# Sound_SCH.net
KiCad netlist of a schematic drawn in Altium Designer
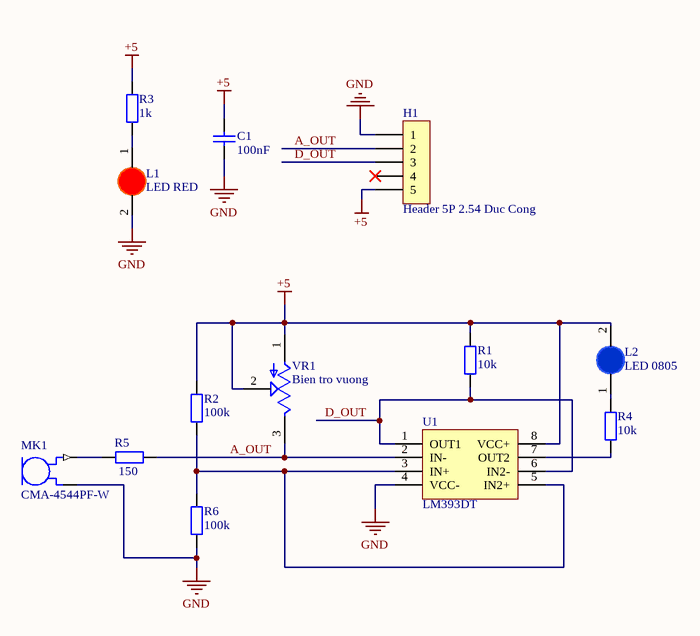
[diagram p0: Sound_SCH.SchDoc]

(export (version "E")
  (design (tool "Eeschema 10.0.6"))
  (components
    (comp (ref "C1")
      (value "100nF")
      (footprint "tu 0603")
      (description "Dán")
      (libsource (lib "namnt_Lib") (part "Tu 0603 104 50V 10%"))
    )
    (comp (ref "H1")
      (value "Header 5P 2.54 Duc Cong")
      (footprint "Header 5P DC 2.54")
      (description "Cắm")
      (libsource (lib "namnt_Lib") (part "Header 5P 2.54 Duc Cong"))
    )
    (comp (ref "L1")
      (value "LED RED")
      (footprint "LED-0805-Red")
      (description "Dán")
      (libsource (lib "namnt_Lib") (part "LED 0805 Do"))
    )
    (comp (ref "L2")
      (value "LED 0805")
      (footprint "LED-0805-Blue")
      (description "Dán")
      (libsource (lib "namnt_Lib") (part "LED 0805 Xanh Duong"))
    )
    (comp (ref "MK1")
      (value "CMA-4544PF-W")
      (footprint "MIC_CMA-4544PF-W")
      (description "9.7 mm, Omnidirectional, PCB Mount, 3.0 Vdc, Electret Condenser Microphone")
      (fields (field (name "MF") "Same Sky"))
      (libsource (lib "namnt_Lib") (part "CMA-4544PF-W"))
    )
    (comp (ref "R1")
      (value "10k")
      (footprint "tro smd 0603")
      (description "Dán")
      (libsource (lib "namnt_Lib") (part "Tro 0603 5% 100k"))
    )
    (comp (ref "R2")
      (value "100k")
      (footprint "tro smd 0603")
      (description "Dán")
      (libsource (lib "namnt_Lib") (part "Tro 0603 5% 100k"))
    )
    (comp (ref "R3")
      (value "1k")
      (footprint "tro smd 0603")
      (description "Dán")
      (libsource (lib "namnt_Lib") (part "Tro 0603 1% 1k"))
    )
    (comp (ref "R4")
      (value "10k")
      (footprint "tro smd 0603")
      (description "Dán")
      (libsource (lib "namnt_Lib") (part "Tro 0603 5% 100k"))
    )
    (comp (ref "R5")
      (value "150")
      (footprint "tro smd 0603")
      (description "Dán")
      (libsource (lib "namnt_Lib") (part "Tro 0603 5% 150R"))
    )
    (comp (ref "R6")
      (value "100k")
      (footprint "tro smd 0603")
      (description "Dán")
      (libsource (lib "namnt_Lib") (part "Tro 0603 5% 100k"))
    )
    (comp (ref "U1")
      (value "LM393DT")
      (footprint "SOIC8_50_328_25X90_SMT")
      (description "Comparator General Purpose CMOS, DTL, ECL, MOS, Open-Collector, TTL 8-SO")
      (fields (field (name "MANUFACTURER") "Texas Instruments"))
      (libsource (lib "namnt_Lib") (part "IC_LM393DT"))
    )
    (comp (ref "VR1")
      (value "Bien tro vuong")
      (footprint "TRIM_3362P-1-102")
      (description "TRIMMER - 1/4in SQ ST CERMET ¦ Bourns 3362P-1-102")
      (fields (field (name "MF") "Bourns") (field (name "MP") "3362P-1-102"))
      (libsource (lib "namnt_Lib") (part "Bien tro vuong"))
    )
  )
  (nets
    (net (code "1") (name "+5") (class "Default")
      (node (ref "C1") (pin "1") (pinfunction "1_1") (pintype "passive"))
      (node (ref "H1") (pin "5") (pinfunction "5_5") (pintype "passive"))
      (node (ref "L2") (pin "2") (pinfunction "K_2") (pintype "passive"))
      (node (ref "R1") (pin "2") (pinfunction "2_2") (pintype "passive"))
      (node (ref "R2") (pin "2") (pinfunction "2_2") (pintype "passive"))
      (node (ref "R3") (pin "2") (pinfunction "2_2") (pintype "passive"))
      (node (ref "U1") (pin "8") (pinfunction "VCC+_8") (pintype "passive"))
      (node (ref "VR1") (pin "1") (pinfunction "CCW_1") (pintype "passive"))
      (node (ref "VR1") (pin "2") (pinfunction "WIPER_2") (pintype "passive"))
    )
    (net (code "2") (name "/A_OUT") (class "Default")
      (node (ref "H1") (pin "2") (pinfunction "2_2") (pintype "passive"))
      (node (ref "R5") (pin "2") (pinfunction "2_2") (pintype "passive"))
      (node (ref "U1") (pin "2") (pinfunction "IN-_2") (pintype "passive"))
      (node (ref "VR1") (pin "3") (pinfunction "CW_3") (pintype "passive"))
    )
    (net (code "3") (name "/D_OUT") (class "Default")
      (node (ref "H1") (pin "3") (pinfunction "3_3") (pintype "passive"))
      (node (ref "R1") (pin "1") (pinfunction "1_1") (pintype "passive"))
      (node (ref "U1") (pin "1") (pinfunction "OUT1_1") (pintype "passive"))
      (node (ref "U1") (pin "6") (pinfunction "IN2-_6") (pintype "passive"))
    )
    (net (code "4") (name "GND") (class "Default")
      (node (ref "C1") (pin "2") (pinfunction "2_2") (pintype "passive"))
      (node (ref "H1") (pin "1") (pinfunction "1_1") (pintype "passive"))
      (node (ref "L1") (pin "2") (pinfunction "K_2") (pintype "passive"))
      (node (ref "MK1") (pin "2") (pinfunction "GND_2") (pintype "power_in"))
      (node (ref "R6") (pin "1") (pinfunction "1_1") (pintype "passive"))
      (node (ref "U1") (pin "4") (pinfunction "VCC-_4") (pintype "passive"))
    )
    (net (code "5") (name "Net-(L1-A)") (class "Default")
      (node (ref "L1") (pin "1") (pinfunction "A_1") (pintype "passive"))
      (node (ref "R3") (pin "1") (pinfunction "1_1") (pintype "passive"))
    )
    (net (code "6") (name "Net-(L2-A)") (class "Default")
      (node (ref "L2") (pin "1") (pinfunction "A_1") (pintype "passive"))
      (node (ref "R4") (pin "2") (pinfunction "2_2") (pintype "passive"))
    )
    (net (code "7") (name "Net-(MK1-OUT)") (class "Default")
      (node (ref "MK1") (pin "1") (pinfunction "OUT_1") (pintype "output"))
      (node (ref "R5") (pin "1") (pinfunction "1_1") (pintype "passive"))
    )
    (net (code "8") (name "Net-(U1-IN+)") (class "Default")
      (node (ref "R2") (pin "1") (pinfunction "1_1") (pintype "passive"))
      (node (ref "R6") (pin "2") (pinfunction "2_2") (pintype "passive"))
      (node (ref "U1") (pin "3") (pinfunction "IN+_3") (pintype "passive"))
      (node (ref "U1") (pin "5") (pinfunction "IN2+_5") (pintype "passive"))
    )
    (net (code "9") (name "Net-(U1-OUT2)") (class "Default")
      (node (ref "R4") (pin "1") (pinfunction "1_1") (pintype "passive"))
      (node (ref "U1") (pin "7") (pinfunction "OUT2_7") (pintype "passive"))
    )
    (net (code "10") (name "unconnected-(H1-Pad4)") (class "Default")
      (node (ref "H1") (pin "4") (pinfunction "4_4") (pintype "passive+no_connect"))
    )
  )
)
